# template_atmega328p.net
KiCad netlist of a schematic drawn in EAGLE
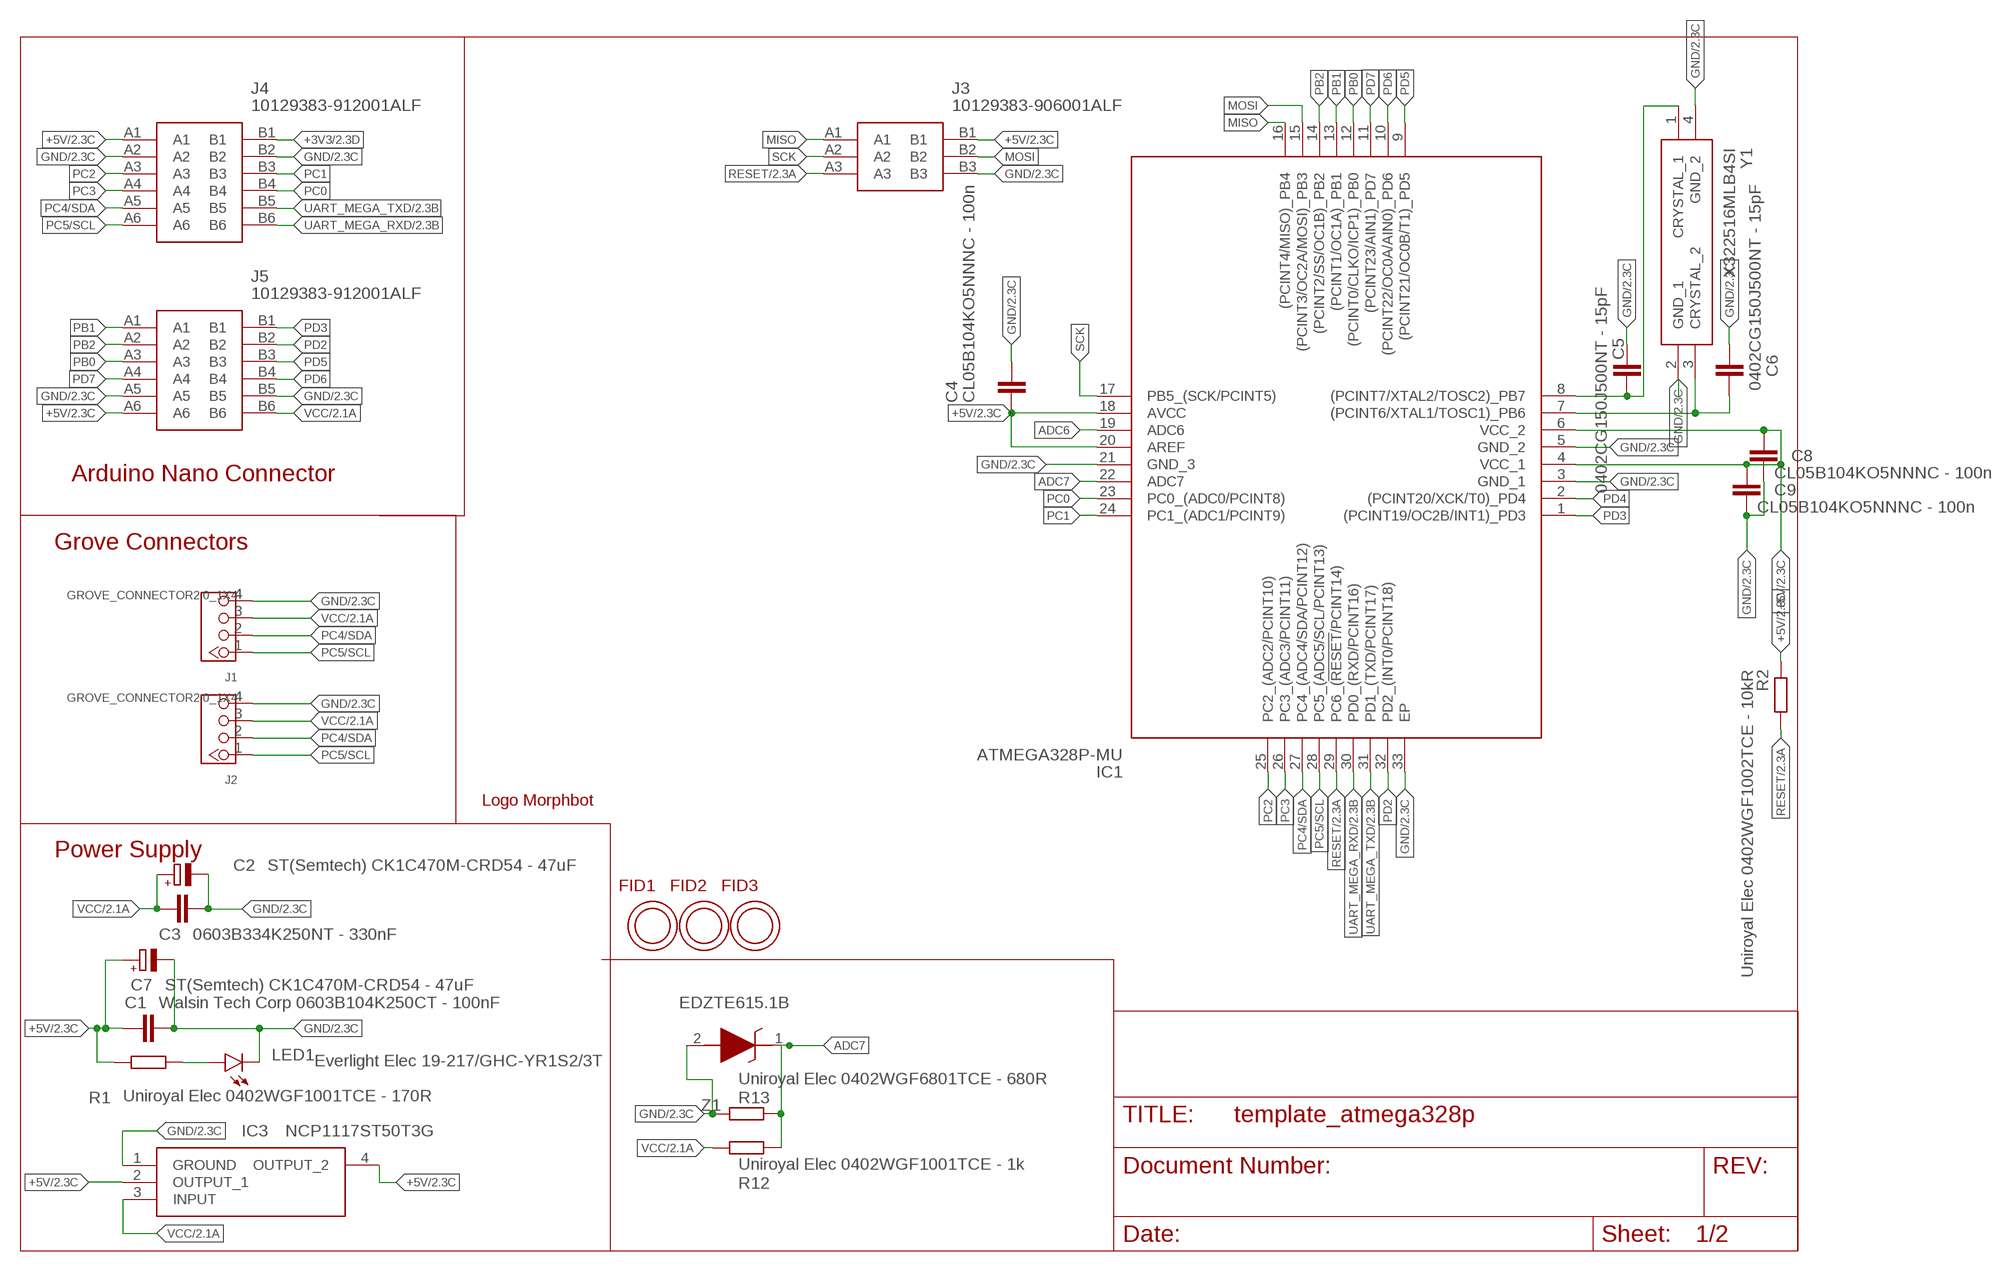
[diagram p0: schematic, sheet 1]
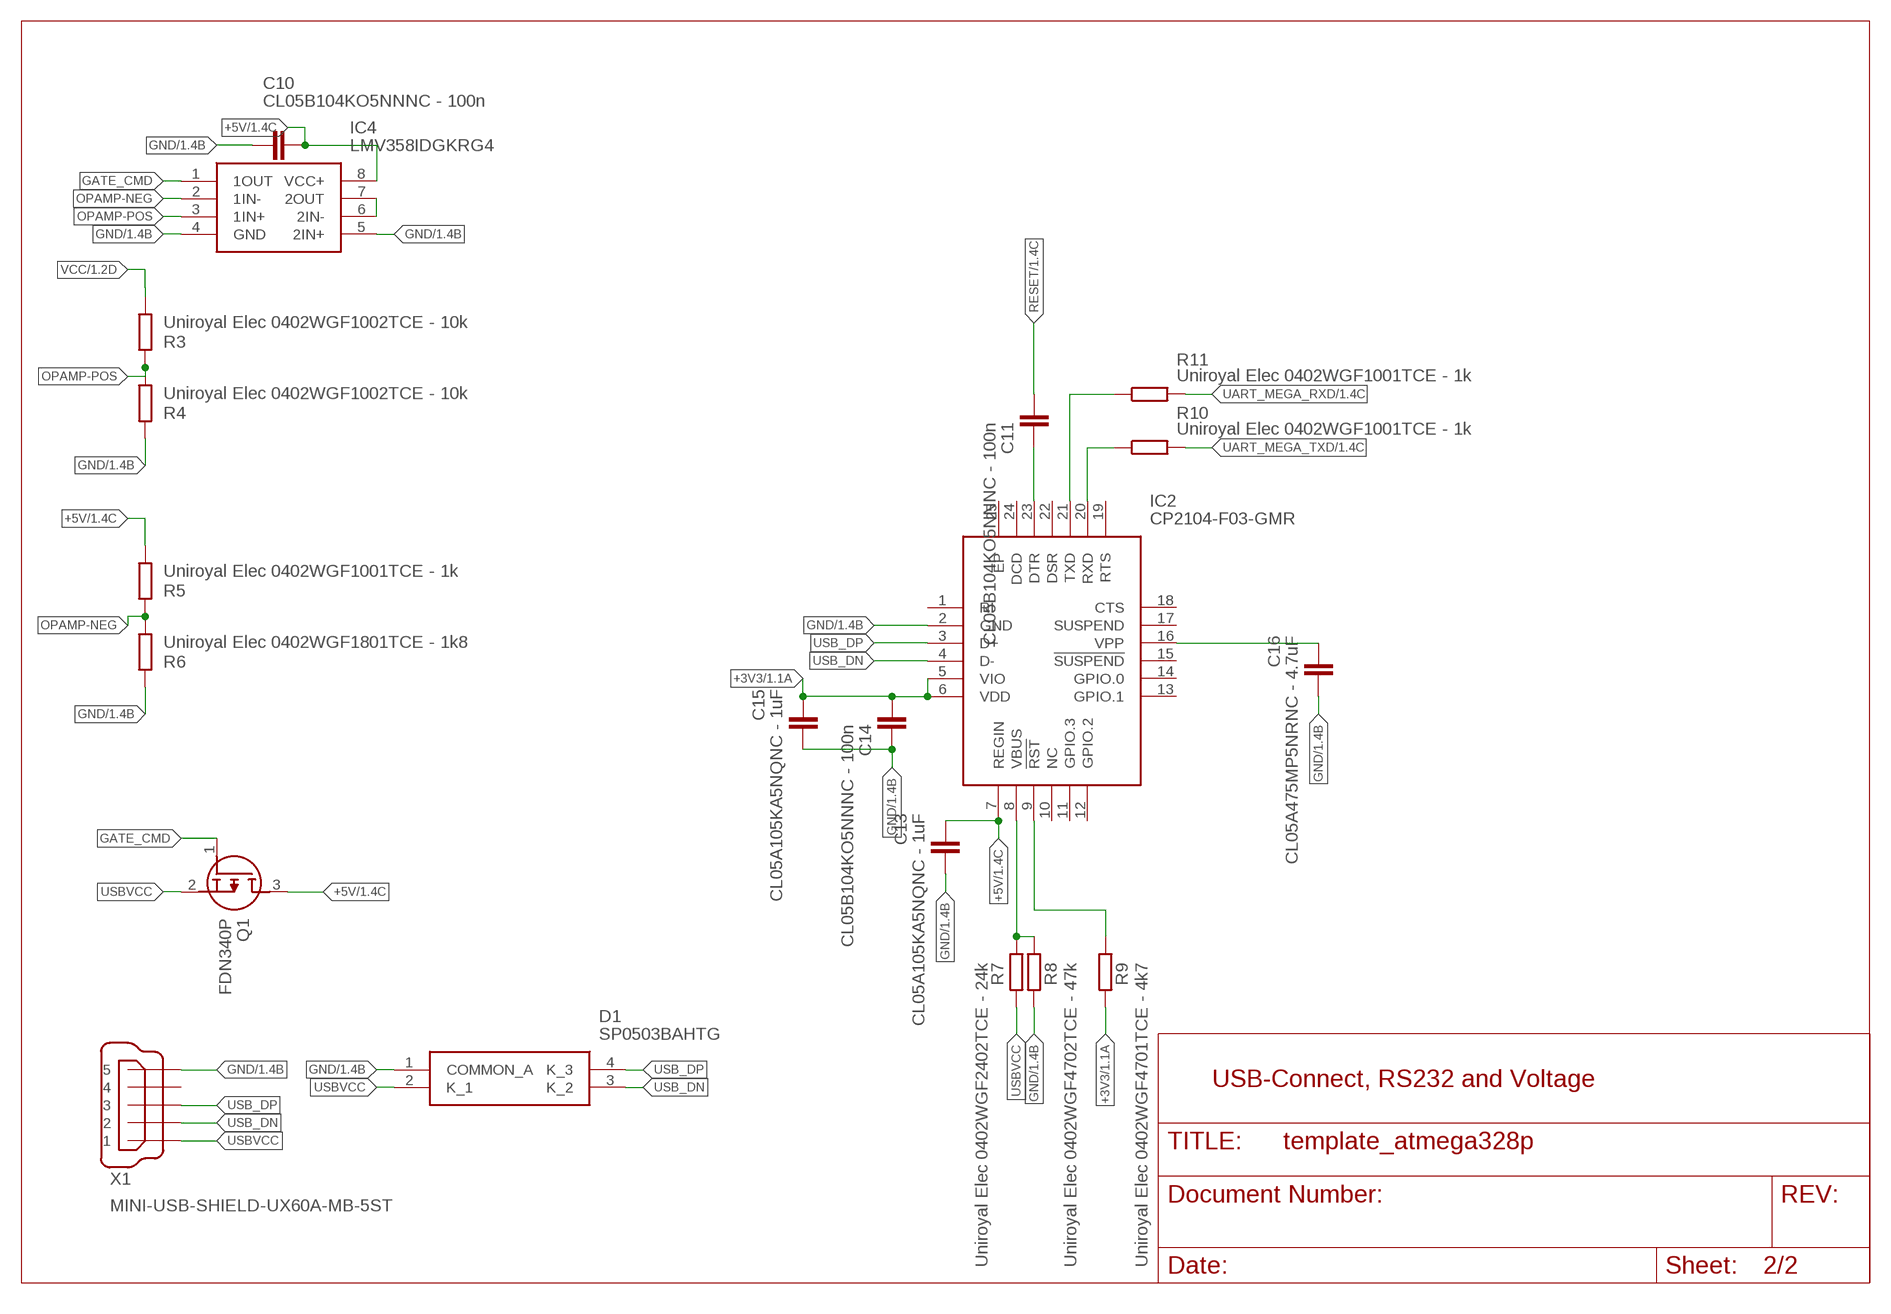
[diagram p1: schematic, sheet 2]

(export (version "E")
  (design (tool "Eeschema 10.0.6"))
  (components
    (comp (ref "C10")
      (value "CL05B104KO5NNNC - 100n")
      (footprint "eagle-import:C0402")
      (libsource (lib "eagle-import") (part "C-EUC0402"))
    )
    (comp (ref "C11")
      (value "CL05B104KO5NNNC - 100n")
      (footprint "eagle-import:C0402")
      (libsource (lib "eagle-import") (part "C-EUC0402"))
    )
    (comp (ref "C13")
      (value "CL05A105KA5NQNC - 1uF")
      (footprint "eagle-import:C0402")
      (libsource (lib "eagle-import") (part "C-EUC0402"))
    )
    (comp (ref "C14")
      (value "CL05B104KO5NNNC - 100n")
      (footprint "eagle-import:C0402")
      (libsource (lib "eagle-import") (part "C-EUC0402"))
    )
    (comp (ref "C15")
      (value "CL05A105KA5NQNC - 1uF")
      (footprint "eagle-import:C0402")
      (libsource (lib "eagle-import") (part "C-EUC0402"))
    )
    (comp (ref "C16")
      (value "CL05A475MP5NRNC - 4.7uF")
      (footprint "eagle-import:C0402")
      (libsource (lib "eagle-import") (part "C-EUC0402"))
    )
    (comp (ref "D1")
      (value "SP0503BAHTG")
      (footprint "eagle-import:SP0503BAHTG")
      (fields (field (name "MOUSER_PART_NUMBER") "576-SP0503BAHTG"))
      (libsource (lib "eagle-import") (part "SP0503BAHTG"))
    )
    (comp (ref "IC2")
      (value "CP2104-F03-GMR")
      (footprint "eagle-import:QFN50P400X400X80-25N")
      (fields (field (name "MOUSER_PART_NUMBER") "634-CP2104-F03-GMR"))
      (libsource (lib "eagle-import") (part "CP2104-F03-GMR"))
    )
    (comp (ref "IC4")
      (value "LMV358IDGKRG4")
      (footprint "eagle-import:SOP65P490X110-8N")
      (fields (field (name "MOUSER_PART_NUMBER") "595-LMV358IDGKRG4"))
      (libsource (lib "eagle-import") (part "LMV358IDGKRG4"))
    )
    (comp (ref "Q1")
      (value "FDN340P")
      (footprint "eagle-import:SOT95P237X112-3N")
      (fields (field (name "MOUSER_PART_NUMBER") "512-FDN340P"))
      (libsource (lib "eagle-import") (part "FDN340P"))
    )
    (comp (ref "R3")
      (value "Uniroyal Elec 0402WGF1002TCE - 10k")
      (footprint "eagle-import:R0402")
      (libsource (lib "eagle-import") (part "R-EU_R0402"))
    )
    (comp (ref "R4")
      (value "Uniroyal Elec 0402WGF1002TCE - 10k")
      (footprint "eagle-import:R0402")
      (libsource (lib "eagle-import") (part "R-EU_R0402"))
    )
    (comp (ref "R5")
      (value "Uniroyal Elec 0402WGF1001TCE - 1k")
      (footprint "eagle-import:R0402")
      (libsource (lib "eagle-import") (part "R-EU_R0402"))
    )
    (comp (ref "R6")
      (value "Uniroyal Elec 0402WGF1801TCE - 1k8")
      (footprint "eagle-import:R0402")
      (libsource (lib "eagle-import") (part "R-EU_R0402"))
    )
    (comp (ref "R7")
      (value "Uniroyal Elec 0402WGF2402TCE - 24k")
      (footprint "eagle-import:R0402")
      (libsource (lib "eagle-import") (part "R-EU_R0402"))
    )
    (comp (ref "R8")
      (value "Uniroyal Elec 0402WGF4702TCE - 47k")
      (footprint "eagle-import:R0402")
      (libsource (lib "eagle-import") (part "R-EU_R0402"))
    )
    (comp (ref "R9")
      (value "Uniroyal Elec 0402WGF4701TCE - 4k7")
      (footprint "eagle-import:R0402")
      (libsource (lib "eagle-import") (part "R-EU_R0402"))
    )
    (comp (ref "R10")
      (value "Uniroyal Elec 0402WGF1001TCE - 1k")
      (footprint "eagle-import:R0402")
      (libsource (lib "eagle-import") (part "R-EU_R0402"))
    )
    (comp (ref "R11")
      (value "Uniroyal Elec 0402WGF1001TCE - 1k")
      (footprint "eagle-import:R0402")
      (libsource (lib "eagle-import") (part "R-EU_R0402"))
    )
    (comp (ref "X1")
      (value "MINI-USB-SHIELD-UX60A-MB-5ST")
      (footprint "eagle-import:UX60A-MB-5ST")
      (libsource (lib "eagle-import") (part "MINI-USB-SHIELD-UX60A-MB-5ST"))
    )
    (comp (ref "C1")
      (value "Walsin Tech Corp 0603B104K250CT - 100nF")
      (footprint "eagle-import:C0603")
      (libsource (lib "eagle-import") (part "C-EUC0603"))
    )
    (comp (ref "C2")
      (value "ST(Semtech) CK1C470M-CRD54 - 47uF")
      (footprint "eagle-import:PANASONIC_C")
      (libsource (lib "eagle-import") (part "CPOL-EUC"))
    )
    (comp (ref "C3")
      (value "0603B334K250NT - 330nF")
      (footprint "eagle-import:C0603")
      (libsource (lib "eagle-import") (part "C-EUC0603"))
    )
    (comp (ref "C4")
      (value "CL05B104KO5NNNC - 100n")
      (footprint "eagle-import:C0402")
      (libsource (lib "eagle-import") (part "C-EUC0402"))
    )
    (comp (ref "C5")
      (value "0402CG150J500NT - 15pF")
      (footprint "eagle-import:C0402")
      (libsource (lib "eagle-import") (part "C-EUC0402"))
    )
    (comp (ref "C6")
      (value "0402CG150J500NT - 15pF")
      (footprint "eagle-import:C0402")
      (libsource (lib "eagle-import") (part "C-EUC0402"))
    )
    (comp (ref "C7")
      (value "ST(Semtech) CK1C470M-CRD54 - 47uF")
      (footprint "eagle-import:PANASONIC_C")
      (libsource (lib "eagle-import") (part "CPOL-EUC"))
    )
    (comp (ref "C8")
      (value "CL05B104KO5NNNC - 100n")
      (footprint "eagle-import:C0402")
      (libsource (lib "eagle-import") (part "C-EUC0402"))
    )
    (comp (ref "C9")
      (value "CL05B104KO5NNNC - 100n")
      (footprint "eagle-import:C0402")
      (libsource (lib "eagle-import") (part "C-EUC0402"))
    )
    (comp (ref "FID1")
      (value "OPEN-PNP-FIDUCIAL")
      (footprint "eagle-import:OPEN-PNP-FIDUCIAL")
      (libsource (lib "eagle-import") (part "OPEN-PNP-FIDUCIAL"))
    )
    (comp (ref "FID2")
      (value "OPEN-PNP-FIDUCIAL")
      (footprint "eagle-import:OPEN-PNP-FIDUCIAL")
      (libsource (lib "eagle-import") (part "OPEN-PNP-FIDUCIAL"))
    )
    (comp (ref "FID3")
      (value "OPEN-PNP-FIDUCIAL")
      (footprint "eagle-import:OPEN-PNP-FIDUCIAL")
      (libsource (lib "eagle-import") (part "OPEN-PNP-FIDUCIAL"))
    )
    (comp (ref "IC1")
      (value "ATMEGA328P-MU")
      (footprint "eagle-import:QFN50P500X500X100-33N")
      (fields (field (name "MOUSER_PART_NUMBER") "556-ATMEGA328P-MU"))
      (libsource (lib "eagle-import") (part "ATMEGA328P-MU"))
    )
    (comp (ref "IC3")
      (value "NCP1117ST50T3G")
      (footprint "eagle-import:SOT230P700X180-4N")
      (fields (field (name "MOUSER_PART_NUMBER") "863-NCP1117ST50T3G"))
      (libsource (lib "eagle-import") (part "NCP1117ST50T3G"))
    )
    (comp (ref "J1")
      (value "GROVE_CONNECTOR2.0_1X4")
      (footprint "eagle-import:2.0_1X4_STRAIGHT")
      (libsource (lib "eagle-import") (part "GROVE_CONNECTOR2.0_1X4"))
    )
    (comp (ref "J2")
      (value "GROVE_CONNECTOR2.0_1X4")
      (footprint "eagle-import:2.0_1X4_STRAIGHT")
      (libsource (lib "eagle-import") (part "GROVE_CONNECTOR2.0_1X4"))
    )
    (comp (ref "J3")
      (value "10129383-906001ALF")
      (footprint "eagle-import:10129383906001ALF")
      (fields (field (name "MOUSER_PART_NUMBER") "649-1012938390601ALF"))
      (libsource (lib "eagle-import") (part "10129383-906001ALF"))
    )
    (comp (ref "J4")
      (value "10129383-912001ALF")
      (footprint "eagle-import:10129383912001ALF")
      (fields (field (name "MOUSER_PART_NUMBER") "649-1012938391201ALF"))
      (libsource (lib "eagle-import") (part "10129383-912001ALF"))
    )
    (comp (ref "J5")
      (value "10129383-912001ALF")
      (footprint "eagle-import:10129383912001ALF")
      (fields (field (name "MOUSER_PART_NUMBER") "649-1012938391201ALF"))
      (libsource (lib "eagle-import") (part "10129383-912001ALF"))
    )
    (comp (ref "LED1")
      (value "Everlight Elec 19-217/GHC-YR1S2/3T")
      (footprint "eagle-import:CHIPLED_0603")
      (libsource (lib "eagle-import") (part "LEDCHIPLED_0603"))
    )
    (comp (ref "R1")
      (value "Uniroyal Elec 0402WGF1001TCE - 170R")
      (footprint "eagle-import:R0402")
      (libsource (lib "eagle-import") (part "R-EU_R0402"))
    )
    (comp (ref "R2")
      (value "Uniroyal Elec 0402WGF1002TCE - 10kR")
      (footprint "eagle-import:R0402")
      (libsource (lib "eagle-import") (part "R-EU_R0402"))
    )
    (comp (ref "R12")
      (value "Uniroyal Elec 0402WGF1001TCE - 1k")
      (footprint "eagle-import:R0402")
      (libsource (lib "eagle-import") (part "R-EU_R0402"))
    )
    (comp (ref "R13")
      (value "Uniroyal Elec 0402WGF6801TCE - 680R")
      (footprint "eagle-import:R0402")
      (libsource (lib "eagle-import") (part "R-EU_R0402"))
    )
    (comp (ref "U$1")
      (value "LOGO_MORPHBOT5MM")
      (footprint "eagle-import:LOGO_MORPHBOT")
      (libsource (lib "eagle-import") (part "LOGO_MORPHBOT5MM"))
    )
    (comp (ref "Y1")
      (value "X322516MLB4SI")
      (footprint "eagle-import:X322516MLB4SI")
      (libsource (lib "eagle-import") (part "X322516MLB4SI"))
    )
    (comp (ref "Z1")
      (value "EDZTE615.1B")
      (footprint "eagle-import:EMD2")
      (fields (field (name "MOUSER_PART_NUMBER") "755-EDZTE615.1B"))
      (libsource (lib "eagle-import") (part "EDZTE615.1B"))
    )
  )
  (nets
    (net (code "1") (name "+3V3") (class "Default")
      (node (ref "C14") (pin "2") (pinfunction "2_2") (pintype "passive"))
      (node (ref "C15") (pin "2") (pinfunction "2_2") (pintype "passive"))
      (node (ref "IC2") (pin "5") (pinfunction "VIO_5") (pintype "bidirectional"))
      (node (ref "IC2") (pin "6") (pinfunction "VDD_6") (pintype "bidirectional"))
      (node (ref "J4") (pin "B1") (pinfunction "B1_B1") (pintype "bidirectional"))
      (node (ref "R9") (pin "2") (pinfunction "2_2") (pintype "passive"))
    )
    (net (code "2") (name "+5V") (class "Default")
      (node (ref "C1") (pin "1") (pinfunction "1_1") (pintype "passive"))
      (node (ref "C10") (pin "2") (pinfunction "2_2") (pintype "passive"))
      (node (ref "C13") (pin "2") (pinfunction "2_2") (pintype "passive"))
      (node (ref "C4") (pin "1") (pinfunction "1_1") (pintype "passive"))
      (node (ref "C7") (pin "+") (pinfunction "+_+") (pintype "passive"))
      (node (ref "C8") (pin "2") (pinfunction "2_2") (pintype "passive"))
      (node (ref "C9") (pin "2") (pinfunction "2_2") (pintype "passive"))
      (node (ref "IC1") (pin "18") (pinfunction "AVCC_18") (pintype "bidirectional"))
      (node (ref "IC1") (pin "20") (pinfunction "AREF_20") (pintype "bidirectional"))
      (node (ref "IC1") (pin "4") (pinfunction "VCC_1_4") (pintype "bidirectional"))
      (node (ref "IC1") (pin "6") (pinfunction "VCC_2_6") (pintype "bidirectional"))
      (node (ref "IC2") (pin "7") (pinfunction "REGIN_7") (pintype "bidirectional"))
      (node (ref "IC3") (pin "2") (pinfunction "OUTPUT_1_2") (pintype "bidirectional"))
      (node (ref "IC3") (pin "4") (pinfunction "OUTPUT_2_4") (pintype "bidirectional"))
      (node (ref "IC4") (pin "8") (pinfunction "VCC+_8") (pintype "bidirectional"))
      (node (ref "J3") (pin "B1") (pinfunction "B1_B1") (pintype "bidirectional"))
      (node (ref "J4") (pin "A1") (pinfunction "A1_A1") (pintype "bidirectional"))
      (node (ref "J5") (pin "A6") (pinfunction "A6_A6") (pintype "bidirectional"))
      (node (ref "Q1") (pin "3") (pinfunction "D_3") (pintype "bidirectional"))
      (node (ref "R1") (pin "2") (pinfunction "2_2") (pintype "passive"))
      (node (ref "R2") (pin "2") (pinfunction "2_2") (pintype "passive"))
      (node (ref "R5") (pin "1") (pinfunction "1_1") (pintype "passive"))
    )
    (net (code "3") (name "ADC6") (class "Default")
      (node (ref "IC1") (pin "19") (pinfunction "ADC6_19") (pintype "bidirectional"))
    )
    (net (code "4") (name "ADC7") (class "Default")
      (node (ref "IC1") (pin "22") (pinfunction "ADC7_22") (pintype "bidirectional"))
      (node (ref "R12") (pin "1") (pinfunction "1_1") (pintype "passive"))
      (node (ref "R13") (pin "2") (pinfunction "2_2") (pintype "passive"))
      (node (ref "Z1") (pin "1") (pinfunction "K_1") (pintype "bidirectional"))
    )
    (net (code "5") (name "GATE_CMD") (class "Default")
      (node (ref "IC4") (pin "1") (pinfunction "1OUT_1") (pintype "bidirectional"))
      (node (ref "Q1") (pin "1") (pinfunction "G_1") (pintype "bidirectional"))
    )
    (net (code "6") (name "GND") (class "Default")
      (node (ref "C1") (pin "2") (pinfunction "2_2") (pintype "passive"))
      (node (ref "C10") (pin "1") (pinfunction "1_1") (pintype "passive"))
      (node (ref "C13") (pin "1") (pinfunction "1_1") (pintype "passive"))
      (node (ref "C14") (pin "1") (pinfunction "1_1") (pintype "passive"))
      (node (ref "C15") (pin "1") (pinfunction "1_1") (pintype "passive"))
      (node (ref "C16") (pin "1") (pinfunction "1_1") (pintype "passive"))
      (node (ref "C2") (pin "-") (pinfunction "-_-") (pintype "passive"))
      (node (ref "C3") (pin "1") (pinfunction "1_1") (pintype "passive"))
      (node (ref "C4") (pin "2") (pinfunction "2_2") (pintype "passive"))
      (node (ref "C5") (pin "1") (pinfunction "1_1") (pintype "passive"))
      (node (ref "C6") (pin "1") (pinfunction "1_1") (pintype "passive"))
      (node (ref "C7") (pin "-") (pinfunction "-_-") (pintype "passive"))
      (node (ref "C8") (pin "1") (pinfunction "1_1") (pintype "passive"))
      (node (ref "C9") (pin "1") (pinfunction "1_1") (pintype "passive"))
      (node (ref "D1") (pin "1") (pinfunction "COMMON_A_1") (pintype "bidirectional"))
      (node (ref "IC1") (pin "21") (pinfunction "GND_3_21") (pintype "bidirectional"))
      (node (ref "IC1") (pin "3") (pinfunction "GND_1_3") (pintype "bidirectional"))
      (node (ref "IC1") (pin "33") (pinfunction "EP_33") (pintype "bidirectional"))
      (node (ref "IC1") (pin "5") (pinfunction "GND_2_5") (pintype "bidirectional"))
      (node (ref "IC2") (pin "2") (pinfunction "GND_2") (pintype "bidirectional"))
      (node (ref "IC3") (pin "1") (pinfunction "GROUND_1") (pintype "bidirectional"))
      (node (ref "IC4") (pin "4") (pinfunction "GND_4") (pintype "bidirectional"))
      (node (ref "IC4") (pin "5") (pinfunction "2IN+_5") (pintype "bidirectional"))
      (node (ref "J1") (pin "4") (pinfunction "4_4") (pintype "bidirectional"))
      (node (ref "J2") (pin "4") (pinfunction "4_4") (pintype "bidirectional"))
      (node (ref "J3") (pin "B3") (pinfunction "B3_B3") (pintype "bidirectional"))
      (node (ref "J4") (pin "A2") (pinfunction "A2_A2") (pintype "bidirectional"))
      (node (ref "J4") (pin "B2") (pinfunction "B2_B2") (pintype "bidirectional"))
      (node (ref "J5") (pin "A5") (pinfunction "A5_A5") (pintype "bidirectional"))
      (node (ref "J5") (pin "B5") (pinfunction "B5_B5") (pintype "bidirectional"))
      (node (ref "LED1") (pin "C") (pinfunction "C_C") (pintype "passive"))
      (node (ref "R13") (pin "1") (pinfunction "1_1") (pintype "passive"))
      (node (ref "R4") (pin "2") (pinfunction "2_2") (pintype "passive"))
      (node (ref "R6") (pin "2") (pinfunction "2_2") (pintype "passive"))
      (node (ref "R8") (pin "2") (pinfunction "2_2") (pintype "passive"))
      (node (ref "X1") (pin "5") (pinfunction "5_5") (pintype "input"))
      (node (ref "Y1") (pin "2") (pinfunction "GND_1_2") (pintype "bidirectional"))
      (node (ref "Y1") (pin "4") (pinfunction "GND_2_4") (pintype "bidirectional"))
      (node (ref "Z1") (pin "2") (pinfunction "A_2") (pintype "bidirectional"))
    )
    (net (code "7") (name "MISO") (class "Default")
      (node (ref "IC1") (pin "16") (pinfunction "(PCINT4/MISO)_PB4_16") (pintype "bidirectional"))
      (node (ref "J3") (pin "A1") (pinfunction "A1_A1") (pintype "bidirectional"))
    )
    (net (code "8") (name "MOSI") (class "Default")
      (node (ref "IC1") (pin "15") (pinfunction "(PCINT3/OC2A/MOSI)_PB3_15") (pintype "bidirectional"))
      (node (ref "J3") (pin "B2") (pinfunction "B2_B2") (pintype "bidirectional"))
    )
    (net (code "9") (name "Net-(IC1-(PCINT6{slash}XTAL1{slash}TOSC1)_PB6)") (class "Default")
      (node (ref "C6") (pin "2") (pinfunction "2_2") (pintype "passive"))
      (node (ref "IC1") (pin "7") (pinfunction "(PCINT6/XTAL1/TOSC1)_PB6_7") (pintype "bidirectional"))
      (node (ref "Y1") (pin "3") (pinfunction "CRYSTAL_2_3") (pintype "bidirectional"))
    )
    (net (code "10") (name "Net-(IC1-(PCINT7{slash}XTAL2{slash}TOSC2)_PB7)") (class "Default")
      (node (ref "C5") (pin "2") (pinfunction "2_2") (pintype "passive"))
      (node (ref "IC1") (pin "8") (pinfunction "(PCINT7/XTAL2/TOSC2)_PB7_8") (pintype "bidirectional"))
      (node (ref "Y1") (pin "1") (pinfunction "CRYSTAL_1_1") (pintype "bidirectional"))
    )
    (net (code "11") (name "Net-(IC2-DTR)") (class "Default")
      (node (ref "C11") (pin "1") (pinfunction "1_1") (pintype "passive"))
      (node (ref "IC2") (pin "23") (pinfunction "DTR_23") (pintype "bidirectional"))
    )
    (net (code "12") (name "Net-(IC2-RXD)") (class "Default")
      (node (ref "IC2") (pin "20") (pinfunction "RXD_20") (pintype "bidirectional"))
      (node (ref "R10") (pin "1") (pinfunction "1_1") (pintype "passive"))
    )
    (net (code "13") (name "Net-(IC2-TXD)") (class "Default")
      (node (ref "IC2") (pin "21") (pinfunction "TXD_21") (pintype "bidirectional"))
      (node (ref "R11") (pin "1") (pinfunction "1_1") (pintype "passive"))
    )
    (net (code "14") (name "Net-(IC2-VBUS)") (class "Default")
      (node (ref "IC2") (pin "8") (pinfunction "VBUS_8") (pintype "bidirectional"))
      (node (ref "R7") (pin "1") (pinfunction "1_1") (pintype "passive"))
      (node (ref "R8") (pin "1") (pinfunction "1_1") (pintype "passive"))
    )
    (net (code "15") (name "Net-(IC2-VPP)") (class "Default")
      (node (ref "C16") (pin "2") (pinfunction "2_2") (pintype "passive"))
      (node (ref "IC2") (pin "16") (pinfunction "VPP_16") (pintype "bidirectional"))
    )
    (net (code "16") (name "Net-(IC2-~{RST})") (class "Default")
      (node (ref "IC2") (pin "9") (pinfunction "~{RST}_9") (pintype "bidirectional"))
      (node (ref "R9") (pin "1") (pinfunction "1_1") (pintype "passive"))
    )
    (net (code "17") (name "Net-(IC4-2IN-)") (class "Default")
      (node (ref "IC4") (pin "6") (pinfunction "2IN-_6") (pintype "bidirectional"))
      (node (ref "IC4") (pin "7") (pinfunction "2OUT_7") (pintype "bidirectional"))
    )
    (net (code "18") (name "Net-(LED1-PadA)") (class "Default")
      (node (ref "LED1") (pin "A") (pinfunction "A_A") (pintype "passive"))
      (node (ref "R1") (pin "1") (pinfunction "1_1") (pintype "passive"))
    )
    (net (code "19") (name "OPAMP-NEG") (class "Default")
      (node (ref "IC4") (pin "2") (pinfunction "1IN-_2") (pintype "bidirectional"))
      (node (ref "R5") (pin "2") (pinfunction "2_2") (pintype "passive"))
      (node (ref "R6") (pin "1") (pinfunction "1_1") (pintype "passive"))
    )
    (net (code "20") (name "OPAMP-POS") (class "Default")
      (node (ref "IC4") (pin "3") (pinfunction "1IN+_3") (pintype "bidirectional"))
      (node (ref "R3") (pin "2") (pinfunction "2_2") (pintype "passive"))
      (node (ref "R4") (pin "1") (pinfunction "1_1") (pintype "passive"))
    )
    (net (code "21") (name "PB0") (class "Default")
      (node (ref "IC1") (pin "12") (pinfunction "(PCINT0/CLKO/ICP1)_PB0_12") (pintype "bidirectional"))
      (node (ref "J5") (pin "A3") (pinfunction "A3_A3") (pintype "bidirectional"))
    )
    (net (code "22") (name "PB1") (class "Default")
      (node (ref "IC1") (pin "13") (pinfunction "(PCINT1/OC1A)_PB1_13") (pintype "bidirectional"))
      (node (ref "J5") (pin "A1") (pinfunction "A1_A1") (pintype "bidirectional"))
    )
    (net (code "23") (name "PB2") (class "Default")
      (node (ref "IC1") (pin "14") (pinfunction "(PCINT2/SS/OC1B)_PB2_14") (pintype "bidirectional"))
      (node (ref "J5") (pin "A2") (pinfunction "A2_A2") (pintype "bidirectional"))
    )
    (net (code "24") (name "PC0") (class "Default")
      (node (ref "IC1") (pin "23") (pinfunction "PC0_(ADC0/PCINT8)_23") (pintype "bidirectional"))
      (node (ref "J4") (pin "B4") (pinfunction "B4_B4") (pintype "bidirectional"))
    )
    (net (code "25") (name "PC1") (class "Default")
      (node (ref "IC1") (pin "24") (pinfunction "PC1_(ADC1/PCINT9)_24") (pintype "bidirectional"))
      (node (ref "J4") (pin "B3") (pinfunction "B3_B3") (pintype "bidirectional"))
    )
    (net (code "26") (name "PC2") (class "Default")
      (node (ref "IC1") (pin "25") (pinfunction "PC2_(ADC2/PCINT10)_25") (pintype "bidirectional"))
      (node (ref "J4") (pin "A3") (pinfunction "A3_A3") (pintype "bidirectional"))
    )
    (net (code "27") (name "PC3") (class "Default")
      (node (ref "IC1") (pin "26") (pinfunction "PC3_(ADC3/PCINT11)_26") (pintype "bidirectional"))
      (node (ref "J4") (pin "A4") (pinfunction "A4_A4") (pintype "bidirectional"))
    )
    (net (code "28") (name "PC4{slash}SDA") (class "Default")
      (node (ref "IC1") (pin "27") (pinfunction "PC4_(ADC4/SDA/PCINT12)_27") (pintype "bidirectional"))
      (node (ref "J1") (pin "2") (pinfunction "2_2") (pintype "bidirectional"))
      (node (ref "J2") (pin "2") (pinfunction "2_2") (pintype "bidirectional"))
      (node (ref "J4") (pin "A5") (pinfunction "A5_A5") (pintype "bidirectional"))
    )
    (net (code "29") (name "PC5{slash}SCL") (class "Default")
      (node (ref "IC1") (pin "28") (pinfunction "PC5_(ADC5/SCL/PCINT13)_28") (pintype "bidirectional"))
      (node (ref "J1") (pin "1") (pinfunction "1_1") (pintype "bidirectional"))
      (node (ref "J2") (pin "1") (pinfunction "1_1") (pintype "bidirectional"))
      (node (ref "J4") (pin "A6") (pinfunction "A6_A6") (pintype "bidirectional"))
    )
    (net (code "30") (name "PD2") (class "Default")
      (node (ref "IC1") (pin "32") (pinfunction "PD2_(INT0/PCINT18)_32") (pintype "bidirectional"))
      (node (ref "J5") (pin "B2") (pinfunction "B2_B2") (pintype "bidirectional"))
    )
    (net (code "31") (name "PD3") (class "Default")
      (node (ref "IC1") (pin "1") (pinfunction "(PCINT19/OC2B/INT1)_PD3_1") (pintype "bidirectional"))
      (node (ref "J5") (pin "B1") (pinfunction "B1_B1") (pintype "bidirectional"))
    )
    (net (code "32") (name "PD4") (class "Default")
      (node (ref "IC1") (pin "2") (pinfunction "(PCINT20/XCK/T0)_PD4_2") (pintype "bidirectional"))
    )
    (net (code "33") (name "PD5") (class "Default")
      (node (ref "IC1") (pin "9") (pinfunction "(PCINT21/OC0B/T1)_PD5_9") (pintype "bidirectional"))
      (node (ref "J5") (pin "B3") (pinfunction "B3_B3") (pintype "bidirectional"))
    )
    (net (code "34") (name "PD6") (class "Default")
      (node (ref "IC1") (pin "10") (pinfunction "(PCINT22/OC0A/AIN0)_PD6_10") (pintype "bidirectional"))
      (node (ref "J5") (pin "B4") (pinfunction "B4_B4") (pintype "bidirectional"))
    )
    (net (code "35") (name "PD7") (class "Default")
      (node (ref "IC1") (pin "11") (pinfunction "(PCINT23/AIN1)_PD7_11") (pintype "bidirectional"))
      (node (ref "J5") (pin "A4") (pinfunction "A4_A4") (pintype "bidirectional"))
    )
    (net (code "36") (name "RESET") (class "Default")
      (node (ref "C11") (pin "2") (pinfunction "2_2") (pintype "passive"))
      (node (ref "IC1") (pin "29") (pinfunction "PC6_(~{RESET}/PCINT14)_29") (pintype "bidirectional"))
      (node (ref "J3") (pin "A3") (pinfunction "A3_A3") (pintype "bidirectional"))
      (node (ref "R2") (pin "1") (pinfunction "1_1") (pintype "passive"))
    )
    (net (code "37") (name "SCK") (class "Default")
      (node (ref "IC1") (pin "17") (pinfunction "PB5_(SCK/PCINT5)_17") (pintype "bidirectional"))
      (node (ref "J3") (pin "A2") (pinfunction "A2_A2") (pintype "bidirectional"))
    )
    (net (code "38") (name "UART_MEGA_RXD") (class "Default")
      (node (ref "IC1") (pin "30") (pinfunction "PD0_(RXD/PCINT16)_30") (pintype "bidirectional"))
      (node (ref "J4") (pin "B6") (pinfunction "B6_B6") (pintype "bidirectional"))
      (node (ref "R11") (pin "2") (pinfunction "2_2") (pintype "passive"))
    )
    (net (code "39") (name "UART_MEGA_TXD") (class "Default")
      (node (ref "IC1") (pin "31") (pinfunction "PD1_(TXD/PCINT17)_31") (pintype "bidirectional"))
      (node (ref "J4") (pin "B5") (pinfunction "B5_B5") (pintype "bidirectional"))
      (node (ref "R10") (pin "2") (pinfunction "2_2") (pintype "passive"))
    )
    (net (code "40") (name "USBVCC") (class "Default")
      (node (ref "D1") (pin "2") (pinfunction "K_1_2") (pintype "bidirectional"))
      (node (ref "Q1") (pin "2") (pinfunction "S_2") (pintype "bidirectional"))
      (node (ref "R7") (pin "2") (pinfunction "2_2") (pintype "passive"))
      (node (ref "X1") (pin "1") (pinfunction "1_1") (pintype "input"))
    )
    (net (code "41") (name "USB_DN") (class "Default")
      (node (ref "D1") (pin "3") (pinfunction "K_2_3") (pintype "bidirectional"))
      (node (ref "IC2") (pin "4") (pinfunction "D-_4") (pintype "bidirectional"))
      (node (ref "X1") (pin "2") (pinfunction "2_2") (pintype "input"))
    )
    (net (code "42") (name "USB_DP") (class "Default")
      (node (ref "D1") (pin "4") (pinfunction "K_3_4") (pintype "bidirectional"))
      (node (ref "IC2") (pin "3") (pinfunction "D+_3") (pintype "bidirectional"))
      (node (ref "X1") (pin "3") (pinfunction "3_3") (pintype "input"))
    )
    (net (code "43") (name "VCC") (class "Default")
      (node (ref "C2") (pin "+") (pinfunction "+_+") (pintype "passive"))
      (node (ref "C3") (pin "2") (pinfunction "2_2") (pintype "passive"))
      (node (ref "IC3") (pin "3") (pinfunction "INPUT_3") (pintype "bidirectional"))
      (node (ref "J1") (pin "3") (pinfunction "3_3") (pintype "bidirectional"))
      (node (ref "J2") (pin "3") (pinfunction "3_3") (pintype "bidirectional"))
      (node (ref "J5") (pin "B6") (pinfunction "B6_B6") (pintype "bidirectional"))
      (node (ref "R12") (pin "2") (pinfunction "2_2") (pintype "passive"))
      (node (ref "R3") (pin "1") (pinfunction "1_1") (pintype "passive"))
    )
    (net (code "44") (name "unconnected-(IC2-CTS-Pad18)") (class "Default")
      (node (ref "IC2") (pin "18") (pinfunction "CTS_18") (pintype "bidirectional"))
    )
    (net (code "45") (name "unconnected-(IC2-DCD-Pad24)") (class "Default")
      (node (ref "IC2") (pin "24") (pinfunction "DCD_24") (pintype "bidirectional"))
    )
    (net (code "46") (name "unconnected-(IC2-DSR-Pad22)") (class "Default")
      (node (ref "IC2") (pin "22") (pinfunction "DSR_22") (pintype "bidirectional"))
    )
    (net (code "47") (name "unconnected-(IC2-EP-Pad25)") (class "Default")
      (node (ref "IC2") (pin "25") (pinfunction "EP_25") (pintype "bidirectional"))
    )
    (net (code "48") (name "unconnected-(IC2-GPIO.0-Pad14)") (class "Default")
      (node (ref "IC2") (pin "14") (pinfunction "GPIO.0_14") (pintype "bidirectional"))
    )
    (net (code "49") (name "unconnected-(IC2-GPIO.1-Pad13)") (class "Default")
      (node (ref "IC2") (pin "13") (pinfunction "GPIO.1_13") (pintype "bidirectional"))
    )
    (net (code "50") (name "unconnected-(IC2-GPIO.2-Pad12)") (class "Default")
      (node (ref "IC2") (pin "12") (pinfunction "GPIO.2_12") (pintype "bidirectional"))
    )
    (net (code "51") (name "unconnected-(IC2-GPIO.3-Pad11)") (class "Default")
      (node (ref "IC2") (pin "11") (pinfunction "GPIO.3_11") (pintype "bidirectional"))
    )
    (net (code "52") (name "unconnected-(IC2-NC-Pad10)") (class "Default")
      (node (ref "IC2") (pin "10") (pinfunction "NC_10") (pintype "no_connect"))
    )
    (net (code "53") (name "unconnected-(IC2-RI-Pad1)") (class "Default")
      (node (ref "IC2") (pin "1") (pinfunction "RI_1") (pintype "bidirectional"))
    )
    (net (code "54") (name "unconnected-(IC2-RTS-Pad19)") (class "Default")
      (node (ref "IC2") (pin "19") (pinfunction "RTS_19") (pintype "bidirectional"))
    )
    (net (code "55") (name "unconnected-(IC2-SUSPEND-Pad17)") (class "Default")
      (node (ref "IC2") (pin "17") (pinfunction "SUSPEND_17") (pintype "bidirectional"))
    )
    (net (code "56") (name "unconnected-(IC2-~{SUSPEND}-Pad15)") (class "Default")
      (node (ref "IC2") (pin "15") (pinfunction "~{SUSPEND}_15") (pintype "bidirectional"))
    )
    (net (code "57") (name "unconnected-(X1-Pad4)") (class "Default")
      (node (ref "X1") (pin "4") (pinfunction "4_4") (pintype "input"))
    )
  )
)
